# 1.net
KiCad netlist of a schematic drawn in EAGLE
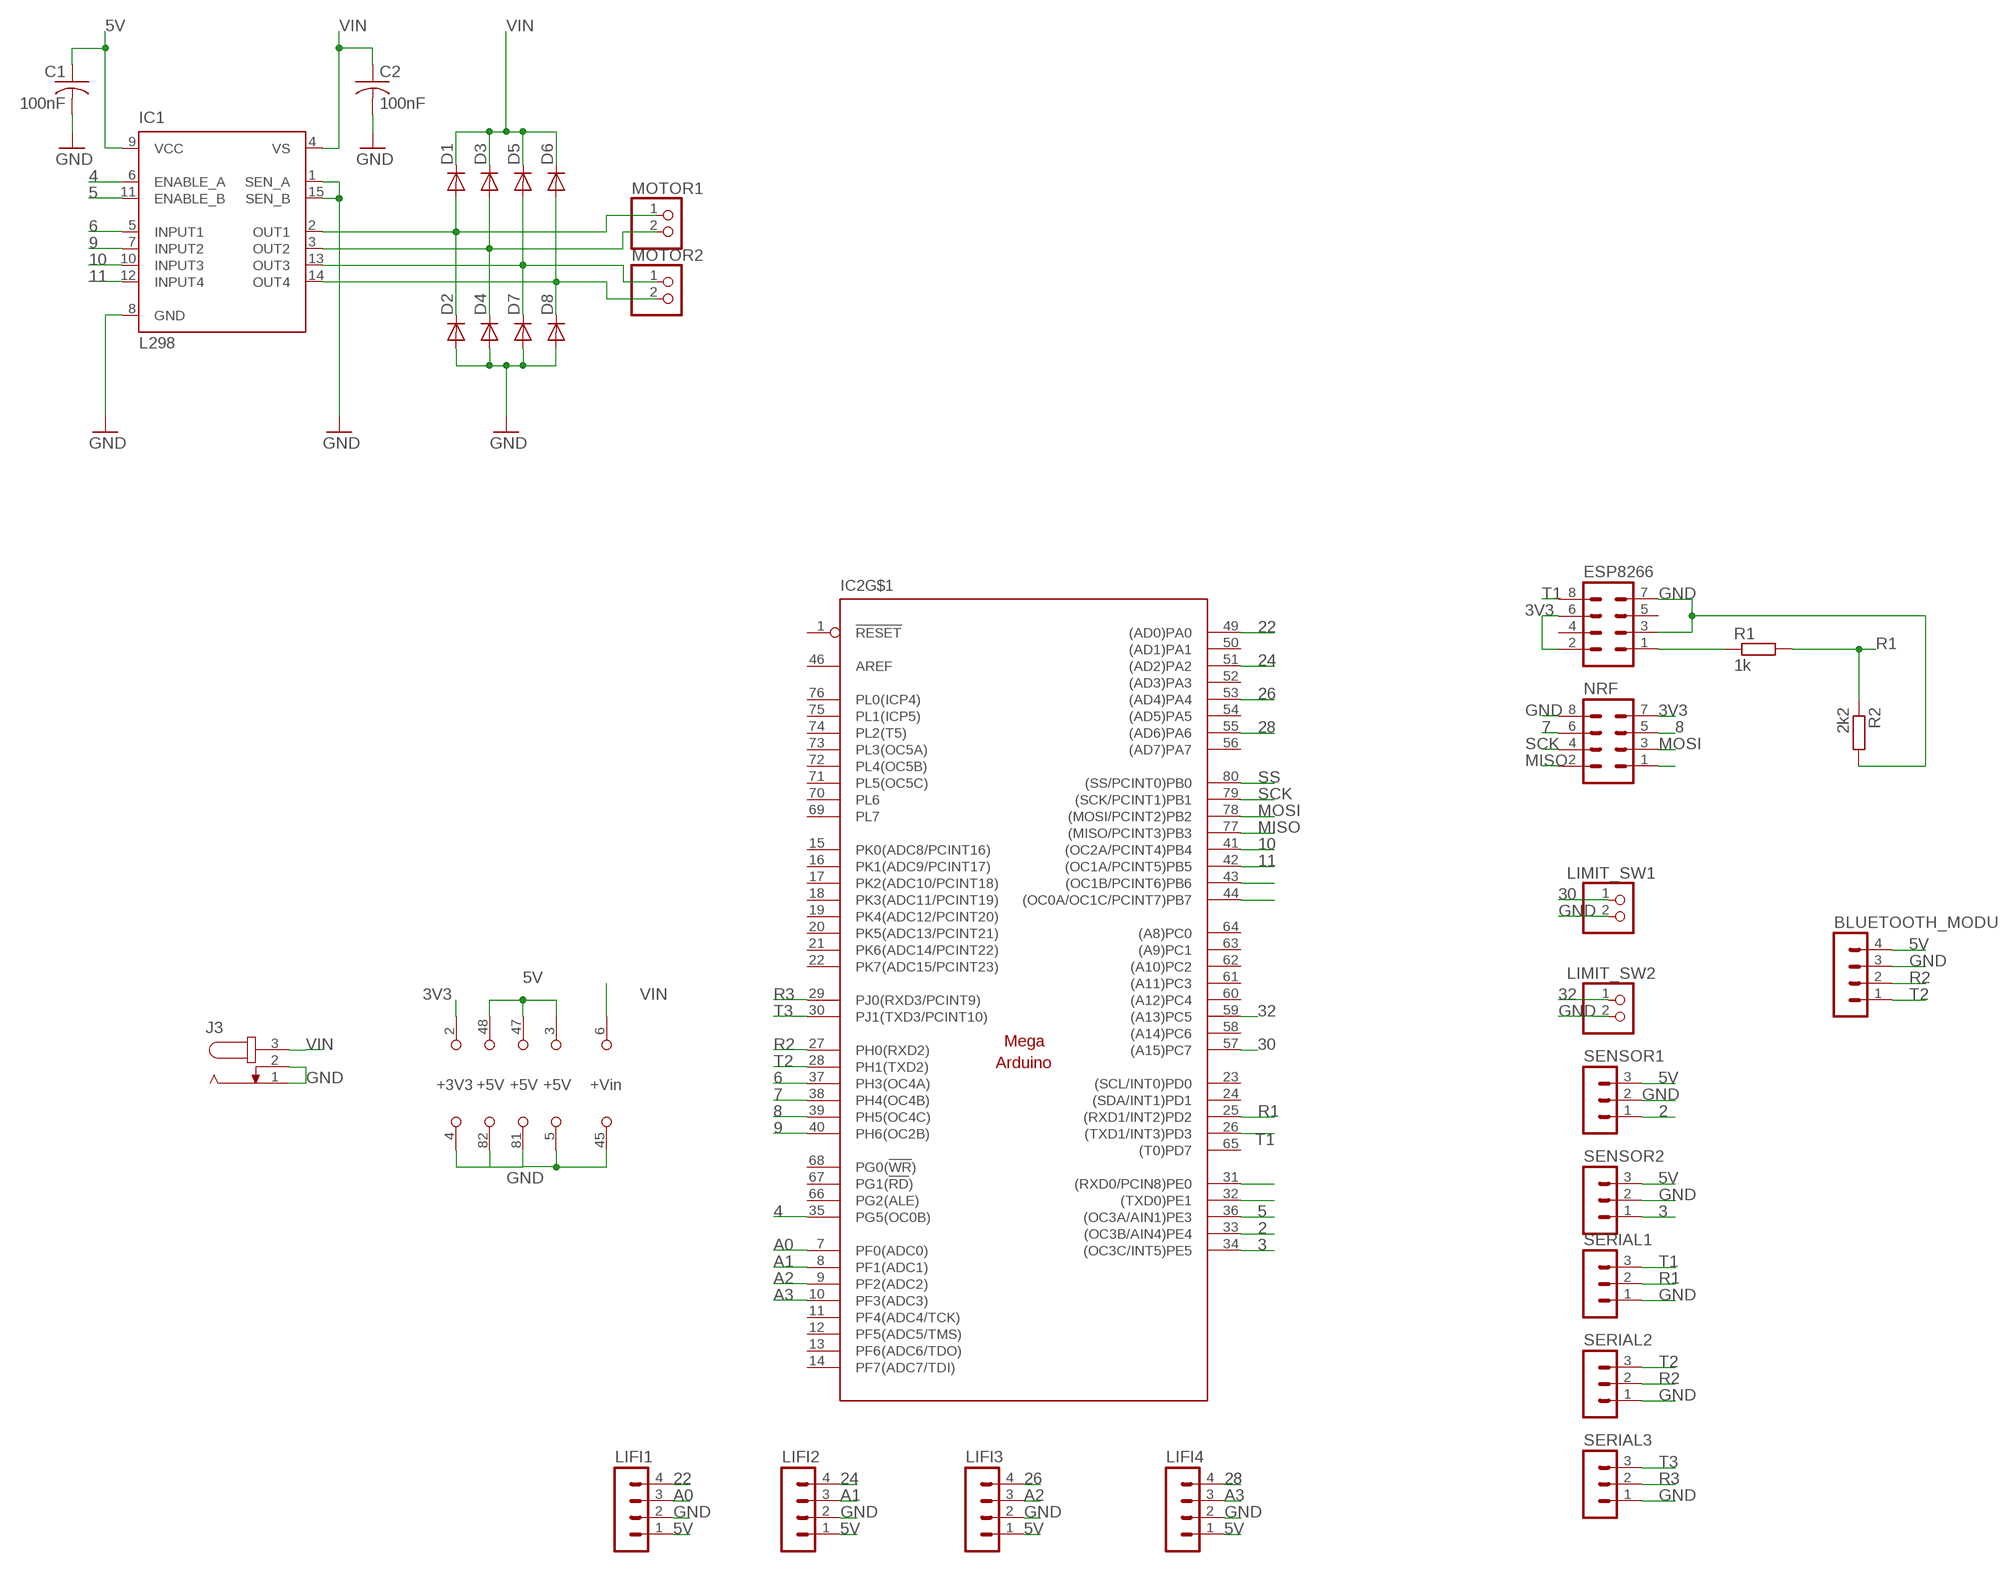
[diagram p0: schematic, sheet 1]

(export (version "E")
  (design (tool "Eeschema 10.0.6"))
  (components
    (comp (ref "BLUETOOTH_MODULE")
      (value "MA04-1")
      (footprint "eagle-import:MA04-1")
      (libsource (lib "eagle-import") (part "MA04-1"))
    )
    (comp (ref "C1")
      (value "100nF")
      (footprint "eagle-import:C050-024X044")
      (libsource (lib "eagle-import") (part "C-US050-024X044"))
    )
    (comp (ref "C2")
      (value "100nF")
      (footprint "eagle-import:C050-024X044")
      (libsource (lib "eagle-import") (part "C-US050-024X044"))
    )
    (comp (ref "D1")
      (value "DIODE-D-5")
      (footprint "eagle-import:D-5")
      (libsource (lib "eagle-import") (part "DIODE-D-5"))
    )
    (comp (ref "D2")
      (value "DIODE-D-5")
      (footprint "eagle-import:D-5")
      (libsource (lib "eagle-import") (part "DIODE-D-5"))
    )
    (comp (ref "D3")
      (value "DIODE-D-5")
      (footprint "eagle-import:D-5")
      (libsource (lib "eagle-import") (part "DIODE-D-5"))
    )
    (comp (ref "D4")
      (value "DIODE-D-5")
      (footprint "eagle-import:D-5")
      (libsource (lib "eagle-import") (part "DIODE-D-5"))
    )
    (comp (ref "D5")
      (value "DIODE-D-5")
      (footprint "eagle-import:D-5")
      (libsource (lib "eagle-import") (part "DIODE-D-5"))
    )
    (comp (ref "D6")
      (value "DIODE-D-5")
      (footprint "eagle-import:D-5")
      (libsource (lib "eagle-import") (part "DIODE-D-5"))
    )
    (comp (ref "D7")
      (value "DIODE-D-5")
      (footprint "eagle-import:D-5")
      (libsource (lib "eagle-import") (part "DIODE-D-5"))
    )
    (comp (ref "D8")
      (value "DIODE-D-5")
      (footprint "eagle-import:D-5")
      (libsource (lib "eagle-import") (part "DIODE-D-5"))
    )
    (comp (ref "ESP8266")
      (value "MA04-2")
      (footprint "eagle-import:MA04-2")
      (libsource (lib "eagle-import") (part "MA04-2"))
    )
    (comp (ref "IC1")
      (value "L298")
      (footprint "eagle-import:MULTIWATT-15")
      (fields (field (name "MPN") "L298N"))
      (libsource (lib "eagle-import") (part "L298"))
    )
    (comp (ref "IC2")
      (value "MEGAARDUINO_21")
      (footprint "eagle-import:MEGA_ARDUINO_1")
      (libsource (lib "eagle-import") (part "MEGAARDUINO_21"))
    )
    (comp (ref "J3")
      (value "JACK-PLUG0")
      (footprint "eagle-import:SPC4077")
      (libsource (lib "eagle-import") (part "JACK-PLUG0"))
    )
    (comp (ref "LIFI1")
      (value "MA04-1")
      (footprint "eagle-import:MA04-1")
      (libsource (lib "eagle-import") (part "MA04-1"))
    )
    (comp (ref "LIFI2")
      (value "MA04-1")
      (footprint "eagle-import:MA04-1")
      (libsource (lib "eagle-import") (part "MA04-1"))
    )
    (comp (ref "LIFI3")
      (value "MA04-1")
      (footprint "eagle-import:MA04-1")
      (libsource (lib "eagle-import") (part "MA04-1"))
    )
    (comp (ref "LIFI4")
      (value "MA04-1")
      (footprint "eagle-import:MA04-1")
      (libsource (lib "eagle-import") (part "MA04-1"))
    )
    (comp (ref "LIMIT_SW1")
      (value "PINHD-1X2")
      (footprint "eagle-import:1X02")
      (libsource (lib "eagle-import") (part "PINHD-1X2"))
    )
    (comp (ref "LIMIT_SW2")
      (value "PINHD-1X2")
      (footprint "eagle-import:1X02")
      (libsource (lib "eagle-import") (part "PINHD-1X2"))
    )
    (comp (ref "MOTOR1")
      (value "PINHD-1X2")
      (footprint "eagle-import:1X02")
      (libsource (lib "eagle-import") (part "PINHD-1X2"))
    )
    (comp (ref "MOTOR2")
      (value "PINHD-1X2")
      (footprint "eagle-import:1X02")
      (libsource (lib "eagle-import") (part "PINHD-1X2"))
    )
    (comp (ref "NRF")
      (value "MA04-2")
      (footprint "eagle-import:MA04-2")
      (libsource (lib "eagle-import") (part "MA04-2"))
    )
    (comp (ref "R1")
      (value "1k")
      (footprint "eagle-import:0204_7")
      (libsource (lib "eagle-import") (part "R-EU_0204/7"))
    )
    (comp (ref "R2")
      (value "2k2")
      (footprint "eagle-import:0204_7")
      (libsource (lib "eagle-import") (part "R-EU_0204/7"))
    )
    (comp (ref "SENSOR1")
      (value "MA03-1")
      (footprint "eagle-import:MA03-1")
      (libsource (lib "eagle-import") (part "MA03-1"))
    )
    (comp (ref "SENSOR2")
      (value "MA03-1")
      (footprint "eagle-import:MA03-1")
      (libsource (lib "eagle-import") (part "MA03-1"))
    )
    (comp (ref "SERIAL1")
      (value "MA03-1")
      (footprint "eagle-import:MA03-1")
      (libsource (lib "eagle-import") (part "MA03-1"))
    )
    (comp (ref "SERIAL2")
      (value "MA03-1")
      (footprint "eagle-import:MA03-1")
      (libsource (lib "eagle-import") (part "MA03-1"))
    )
    (comp (ref "SERIAL3")
      (value "MA03-1")
      (footprint "eagle-import:MA03-1")
      (libsource (lib "eagle-import") (part "MA03-1"))
    )
  )
  (nets
    (net (code "1") (name "/2") (class "Default")
      (node (ref "IC2") (pin "33") (pinfunction "(OC3B/AIN4)PE4_33") (pintype "bidirectional"))
      (node (ref "SENSOR1") (pin "1") (pinfunction "1_1") (pintype "passive"))
    )
    (net (code "2") (name "/3") (class "Default")
      (node (ref "IC2") (pin "34") (pinfunction "(OC3C/INT5)PE5_34") (pintype "bidirectional"))
      (node (ref "SENSOR2") (pin "1") (pinfunction "1_1") (pintype "passive"))
    )
    (net (code "3") (name "/3V3") (class "Default")
      (node (ref "ESP8266") (pin "2") (pinfunction "2_2") (pintype "passive"))
      (node (ref "ESP8266") (pin "6") (pinfunction "6_6") (pintype "passive"))
      (node (ref "IC2") (pin "2") (pinfunction "+3V3_2") (pintype "power_in"))
      (node (ref "NRF") (pin "7") (pinfunction "7_7") (pintype "passive"))
    )
    (net (code "4") (name "/4") (class "Default")
      (node (ref "IC1") (pin "6") (pinfunction "ENABLE_A_6") (pintype "input"))
      (node (ref "IC2") (pin "35") (pinfunction "PG5(OC0B)_35") (pintype "bidirectional"))
    )
    (net (code "5") (name "/5") (class "Default")
      (node (ref "IC1") (pin "11") (pinfunction "ENABLE_B_11") (pintype "input"))
      (node (ref "IC2") (pin "36") (pinfunction "(OC3A/AIN1)PE3_36") (pintype "bidirectional"))
    )
    (net (code "6") (name "/5V") (class "Default")
      (node (ref "BLUETOOTH_MODULE") (pin "4") (pinfunction "4_4") (pintype "passive"))
      (node (ref "C1") (pin "1") (pinfunction "1_1") (pintype "passive"))
      (node (ref "IC1") (pin "9") (pinfunction "VCC_9") (pintype "power_in"))
      (node (ref "IC2") (pin "3") (pinfunction "+5V_3") (pintype "power_in"))
      (node (ref "IC2") (pin "47") (pinfunction "+5V_47") (pintype "power_in"))
      (node (ref "IC2") (pin "48") (pinfunction "+5V_48") (pintype "power_in"))
      (node (ref "LIFI1") (pin "1") (pinfunction "1_1") (pintype "passive"))
      (node (ref "LIFI2") (pin "1") (pinfunction "1_1") (pintype "passive"))
      (node (ref "LIFI3") (pin "1") (pinfunction "1_1") (pintype "passive"))
      (node (ref "LIFI4") (pin "1") (pinfunction "1_1") (pintype "passive"))
      (node (ref "SENSOR1") (pin "3") (pinfunction "3_3") (pintype "passive"))
      (node (ref "SENSOR2") (pin "3") (pinfunction "3_3") (pintype "passive"))
    )
    (net (code "7") (name "/6") (class "Default")
      (node (ref "IC1") (pin "5") (pinfunction "INPUT1_5") (pintype "input"))
      (node (ref "IC2") (pin "37") (pinfunction "PH3(OC4A)_37") (pintype "bidirectional"))
    )
    (net (code "8") (name "/7") (class "Default")
      (node (ref "IC2") (pin "38") (pinfunction "PH4(OC4B)_38") (pintype "bidirectional"))
      (node (ref "NRF") (pin "6") (pinfunction "6_6") (pintype "passive"))
    )
    (net (code "9") (name "/8") (class "Default")
      (node (ref "IC2") (pin "39") (pinfunction "PH5(OC4C)_39") (pintype "bidirectional"))
      (node (ref "NRF") (pin "5") (pinfunction "5_5") (pintype "passive"))
    )
    (net (code "10") (name "/9") (class "Default")
      (node (ref "IC1") (pin "7") (pinfunction "INPUT2_7") (pintype "input"))
      (node (ref "IC2") (pin "40") (pinfunction "PH6(OC2B)_40") (pintype "bidirectional"))
    )
    (net (code "11") (name "/10") (class "Default")
      (node (ref "IC1") (pin "10") (pinfunction "INPUT3_10") (pintype "input"))
      (node (ref "IC2") (pin "41") (pinfunction "(OC2A/PCINT4)PB4_41") (pintype "bidirectional"))
    )
    (net (code "12") (name "/11") (class "Default")
      (node (ref "IC1") (pin "12") (pinfunction "INPUT4_12") (pintype "input"))
      (node (ref "IC2") (pin "42") (pinfunction "(OC1A/PCINT5)PB5_42") (pintype "bidirectional"))
    )
    (net (code "13") (name "/22") (class "Default")
      (node (ref "IC2") (pin "49") (pinfunction "(AD0)PA0_49") (pintype "bidirectional"))
      (node (ref "LIFI1") (pin "4") (pinfunction "4_4") (pintype "passive"))
    )
    (net (code "14") (name "/24") (class "Default")
      (node (ref "IC2") (pin "51") (pinfunction "(AD2)PA2_51") (pintype "bidirectional"))
      (node (ref "LIFI2") (pin "4") (pinfunction "4_4") (pintype "passive"))
    )
    (net (code "15") (name "/26") (class "Default")
      (node (ref "IC2") (pin "53") (pinfunction "(AD4)PA4_53") (pintype "bidirectional"))
      (node (ref "LIFI3") (pin "4") (pinfunction "4_4") (pintype "passive"))
    )
    (net (code "16") (name "/28") (class "Default")
      (node (ref "IC2") (pin "55") (pinfunction "(AD6)PA6_55") (pintype "bidirectional"))
      (node (ref "LIFI4") (pin "4") (pinfunction "4_4") (pintype "passive"))
    )
    (net (code "17") (name "/30") (class "Default")
      (node (ref "IC2") (pin "57") (pinfunction "(A15)PC7_57") (pintype "bidirectional"))
      (node (ref "LIMIT_SW1") (pin "1") (pinfunction "1_1") (pintype "passive"))
    )
    (net (code "18") (name "/32") (class "Default")
      (node (ref "IC2") (pin "59") (pinfunction "(A13)PC5_59") (pintype "bidirectional"))
      (node (ref "LIMIT_SW2") (pin "1") (pinfunction "1_1") (pintype "passive"))
    )
    (net (code "19") (name "/A0") (class "Default")
      (node (ref "IC2") (pin "7") (pinfunction "PF0(ADC0)_7") (pintype "bidirectional"))
      (node (ref "LIFI1") (pin "3") (pinfunction "3_3") (pintype "passive"))
    )
    (net (code "20") (name "/A1") (class "Default")
      (node (ref "IC2") (pin "8") (pinfunction "PF1(ADC1)_8") (pintype "bidirectional"))
      (node (ref "LIFI2") (pin "3") (pinfunction "3_3") (pintype "passive"))
    )
    (net (code "21") (name "/A2") (class "Default")
      (node (ref "IC2") (pin "9") (pinfunction "PF2(ADC2)_9") (pintype "bidirectional"))
      (node (ref "LIFI3") (pin "3") (pinfunction "3_3") (pintype "passive"))
    )
    (net (code "22") (name "/A3") (class "Default")
      (node (ref "IC2") (pin "10") (pinfunction "PF3(ADC3)_10") (pintype "bidirectional"))
      (node (ref "LIFI4") (pin "3") (pinfunction "3_3") (pintype "passive"))
    )
    (net (code "23") (name "/MISO") (class "Default")
      (node (ref "IC2") (pin "77") (pinfunction "(MISO/PCINT3)PB3_77") (pintype "bidirectional"))
      (node (ref "NRF") (pin "2") (pinfunction "2_2") (pintype "passive"))
    )
    (net (code "24") (name "/MOSI") (class "Default")
      (node (ref "IC2") (pin "78") (pinfunction "(MOSI/PCINT2)PB2_78") (pintype "bidirectional"))
      (node (ref "NRF") (pin "3") (pinfunction "3_3") (pintype "passive"))
    )
    (net (code "25") (name "/R1") (class "Default")
      (node (ref "IC2") (pin "25") (pinfunction "(RXD1/INT2)PD2_25") (pintype "bidirectional"))
      (node (ref "R1") (pin "2") (pinfunction "2_2") (pintype "passive"))
      (node (ref "R2") (pin "1") (pinfunction "1_1") (pintype "passive"))
      (node (ref "SERIAL1") (pin "2") (pinfunction "2_2") (pintype "passive"))
    )
    (net (code "26") (name "/R2") (class "Default")
      (node (ref "BLUETOOTH_MODULE") (pin "2") (pinfunction "2_2") (pintype "passive"))
      (node (ref "IC2") (pin "27") (pinfunction "PH0(RXD2)_27") (pintype "bidirectional"))
      (node (ref "SERIAL2") (pin "2") (pinfunction "2_2") (pintype "passive"))
    )
    (net (code "27") (name "/R3") (class "Default")
      (node (ref "IC2") (pin "29") (pinfunction "PJ0(RXD3/PCINT9)_29") (pintype "bidirectional"))
      (node (ref "SERIAL3") (pin "2") (pinfunction "2_2") (pintype "passive"))
    )
    (net (code "28") (name "/SCK") (class "Default")
      (node (ref "IC2") (pin "79") (pinfunction "(SCK/PCINT1)PB1_79") (pintype "bidirectional"))
      (node (ref "NRF") (pin "4") (pinfunction "4_4") (pintype "passive"))
    )
    (net (code "29") (name "/SS") (class "Default")
      (node (ref "IC2") (pin "80") (pinfunction "(SS/PCINT0)PB0_80") (pintype "bidirectional"))
    )
    (net (code "30") (name "/T1") (class "Default")
      (node (ref "ESP8266") (pin "8") (pinfunction "8_8") (pintype "passive"))
      (node (ref "IC2") (pin "26") (pinfunction "(TXD1/INT3)PD3_26") (pintype "bidirectional"))
      (node (ref "SERIAL1") (pin "3") (pinfunction "3_3") (pintype "passive"))
    )
    (net (code "31") (name "/T2") (class "Default")
      (node (ref "BLUETOOTH_MODULE") (pin "1") (pinfunction "1_1") (pintype "passive"))
      (node (ref "IC2") (pin "28") (pinfunction "PH1(TXD2)_28") (pintype "bidirectional"))
      (node (ref "SERIAL2") (pin "3") (pinfunction "3_3") (pintype "passive"))
    )
    (net (code "32") (name "/T3") (class "Default")
      (node (ref "IC2") (pin "30") (pinfunction "PJ1(TXD3/PCINT10)_30") (pintype "bidirectional"))
      (node (ref "SERIAL3") (pin "3") (pinfunction "3_3") (pintype "passive"))
    )
    (net (code "33") (name "/VIN") (class "Default")
      (node (ref "C2") (pin "1") (pinfunction "1_1") (pintype "passive"))
      (node (ref "D1") (pin "C") (pinfunction "C_C") (pintype "passive"))
      (node (ref "D3") (pin "C") (pinfunction "C_C") (pintype "passive"))
      (node (ref "D5") (pin "C") (pinfunction "C_C") (pintype "passive"))
      (node (ref "D6") (pin "C") (pinfunction "C_C") (pintype "passive"))
      (node (ref "IC1") (pin "4") (pinfunction "VS_4") (pintype "power_in"))
      (node (ref "IC2") (pin "6") (pinfunction "+VIN_6") (pintype "power_in"))
      (node (ref "J3") (pin "3") (pinfunction "3_3") (pintype "passive"))
    )
    (net (code "34") (name "GND") (class "Default")
      (node (ref "BLUETOOTH_MODULE") (pin "3") (pinfunction "3_3") (pintype "passive"))
      (node (ref "C1") (pin "2") (pinfunction "2_2") (pintype "passive"))
      (node (ref "C2") (pin "2") (pinfunction "2_2") (pintype "passive"))
      (node (ref "D2") (pin "A") (pinfunction "A_A") (pintype "passive"))
      (node (ref "D4") (pin "A") (pinfunction "A_A") (pintype "passive"))
      (node (ref "D7") (pin "A") (pinfunction "A_A") (pintype "passive"))
      (node (ref "D8") (pin "A") (pinfunction "A_A") (pintype "passive"))
      (node (ref "ESP8266") (pin "3") (pinfunction "3_3") (pintype "passive"))
      (node (ref "ESP8266") (pin "7") (pinfunction "7_7") (pintype "passive"))
      (node (ref "IC1") (pin "1") (pinfunction "SEN_A_1") (pintype "input"))
      (node (ref "IC1") (pin "15") (pinfunction "SEN_B_15") (pintype "input"))
      (node (ref "IC1") (pin "8") (pinfunction "GND_8") (pintype "power_in"))
      (node (ref "IC2") (pin "4") (pinfunction "GND_4") (pintype "power_in"))
      (node (ref "IC2") (pin "45") (pinfunction "GND_45") (pintype "power_in"))
      (node (ref "IC2") (pin "5") (pinfunction "GND_5") (pintype "power_in"))
      (node (ref "IC2") (pin "81") (pinfunction "GND_81") (pintype "power_in"))
      (node (ref "IC2") (pin "82") (pinfunction "GND_82") (pintype "power_in"))
      (node (ref "J3") (pin "1") (pinfunction "1_1") (pintype "passive"))
      (node (ref "J3") (pin "2") (pinfunction "2_2") (pintype "passive"))
      (node (ref "LIFI1") (pin "2") (pinfunction "2_2") (pintype "passive"))
      (node (ref "LIFI2") (pin "2") (pinfunction "2_2") (pintype "passive"))
      (node (ref "LIFI3") (pin "2") (pinfunction "2_2") (pintype "passive"))
      (node (ref "LIFI4") (pin "2") (pinfunction "2_2") (pintype "passive"))
      (node (ref "LIMIT_SW1") (pin "2") (pinfunction "2_2") (pintype "passive"))
      (node (ref "LIMIT_SW2") (pin "2") (pinfunction "2_2") (pintype "passive"))
      (node (ref "NRF") (pin "8") (pinfunction "8_8") (pintype "passive"))
      (node (ref "R2") (pin "2") (pinfunction "2_2") (pintype "passive"))
      (node (ref "SENSOR1") (pin "2") (pinfunction "2_2") (pintype "passive"))
      (node (ref "SENSOR2") (pin "2") (pinfunction "2_2") (pintype "passive"))
      (node (ref "SERIAL1") (pin "1") (pinfunction "1_1") (pintype "passive"))
      (node (ref "SERIAL2") (pin "1") (pinfunction "1_1") (pintype "passive"))
      (node (ref "SERIAL3") (pin "1") (pinfunction "1_1") (pintype "passive"))
    )
    (net (code "35") (name "Net-(ESP8266-Pad1)") (class "Default")
      (node (ref "ESP8266") (pin "1") (pinfunction "1_1") (pintype "passive"))
      (node (ref "R1") (pin "1") (pinfunction "1_1") (pintype "passive"))
    )
    (net (code "36") (name "Net-(IC1-OUT1)") (class "Default")
      (node (ref "D1") (pin "A") (pinfunction "A_A") (pintype "passive"))
      (node (ref "D2") (pin "C") (pinfunction "C_C") (pintype "passive"))
      (node (ref "IC1") (pin "2") (pinfunction "OUT1_2") (pintype "output"))
      (node (ref "MOTOR1") (pin "1") (pinfunction "1_1") (pintype "passive"))
    )
    (net (code "37") (name "Net-(IC1-OUT2)") (class "Default")
      (node (ref "D3") (pin "A") (pinfunction "A_A") (pintype "passive"))
      (node (ref "D4") (pin "C") (pinfunction "C_C") (pintype "passive"))
      (node (ref "IC1") (pin "3") (pinfunction "OUT2_3") (pintype "output"))
      (node (ref "MOTOR1") (pin "2") (pinfunction "2_2") (pintype "passive"))
    )
    (net (code "38") (name "Net-(IC1-OUT3)") (class "Default")
      (node (ref "D5") (pin "A") (pinfunction "A_A") (pintype "passive"))
      (node (ref "D7") (pin "C") (pinfunction "C_C") (pintype "passive"))
      (node (ref "IC1") (pin "13") (pinfunction "OUT3_13") (pintype "output"))
      (node (ref "MOTOR2") (pin "1") (pinfunction "1_1") (pintype "passive"))
    )
    (net (code "39") (name "Net-(IC1-OUT4)") (class "Default")
      (node (ref "D6") (pin "A") (pinfunction "A_A") (pintype "passive"))
      (node (ref "D8") (pin "C") (pinfunction "C_C") (pintype "passive"))
      (node (ref "IC1") (pin "14") (pinfunction "OUT4_14") (pintype "output"))
      (node (ref "MOTOR2") (pin "2") (pinfunction "2_2") (pintype "passive"))
    )
    (net (code "40") (name "unconnected-(ESP8266-Pad4)") (class "Default")
      (node (ref "ESP8266") (pin "4") (pinfunction "4_4") (pintype "passive"))
    )
    (net (code "41") (name "unconnected-(ESP8266-Pad5)") (class "Default")
      (node (ref "ESP8266") (pin "5") (pinfunction "5_5") (pintype "passive"))
    )
    (net (code "42") (name "unconnected-(IC2A-(A8)PC0-Pad64)") (class "Default")
      (node (ref "IC2") (pin "64") (pinfunction "(A8)PC0_64") (pintype "bidirectional"))
    )
    (net (code "43") (name "unconnected-(IC2A-(A9)PC1-Pad63)") (class "Default")
      (node (ref "IC2") (pin "63") (pinfunction "(A9)PC1_63") (pintype "bidirectional"))
    )
    (net (code "44") (name "unconnected-(IC2A-(A10)PC2-Pad62)") (class "Default")
      (node (ref "IC2") (pin "62") (pinfunction "(A10)PC2_62") (pintype "bidirectional"))
    )
    (net (code "45") (name "unconnected-(IC2A-(A11)PC3-Pad61)") (class "Default")
      (node (ref "IC2") (pin "61") (pinfunction "(A11)PC3_61") (pintype "bidirectional"))
    )
    (net (code "46") (name "unconnected-(IC2A-(A12)PC4-Pad60)") (class "Default")
      (node (ref "IC2") (pin "60") (pinfunction "(A12)PC4_60") (pintype "bidirectional"))
    )
    (net (code "47") (name "unconnected-(IC2A-(A14)PC6-Pad58)") (class "Default")
      (node (ref "IC2") (pin "58") (pinfunction "(A14)PC6_58") (pintype "bidirectional"))
    )
    (net (code "48") (name "unconnected-(IC2A-(AD1)PA1-Pad50)") (class "Default")
      (node (ref "IC2") (pin "50") (pinfunction "(AD1)PA1_50") (pintype "bidirectional"))
    )
    (net (code "49") (name "unconnected-(IC2A-(AD3)PA3-Pad52)") (class "Default")
      (node (ref "IC2") (pin "52") (pinfunction "(AD3)PA3_52") (pintype "bidirectional"))
    )
    (net (code "50") (name "unconnected-(IC2A-(AD5)PA5-Pad54)") (class "Default")
      (node (ref "IC2") (pin "54") (pinfunction "(AD5)PA5_54") (pintype "bidirectional"))
    )
    (net (code "51") (name "unconnected-(IC2A-(AD7)PA7-Pad56)") (class "Default")
      (node (ref "IC2") (pin "56") (pinfunction "(AD7)PA7_56") (pintype "bidirectional"))
    )
    (net (code "52") (name "unconnected-(IC2A-(OC0A{slash}OC1C{slash}PCINT7)PB7-Pad44)") (class "Default")
      (node (ref "IC2") (pin "44") (pinfunction "(OC0A/OC1C/PCINT7)PB7_44") (pintype "bidirectional"))
    )
    (net (code "53") (name "unconnected-(IC2A-(OC1B{slash}PCINT6)PB6-Pad43)") (class "Default")
      (node (ref "IC2") (pin "43") (pinfunction "(OC1B/PCINT6)PB6_43") (pintype "bidirectional"))
    )
    (net (code "54") (name "unconnected-(IC2A-(RXD0{slash}PCIN8)PE0-Pad31)") (class "Default")
      (node (ref "IC2") (pin "31") (pinfunction "(RXD0/PCIN8)PE0_31") (pintype "bidirectional"))
    )
    (net (code "55") (name "unconnected-(IC2A-(SCL{slash}INT0)PD0-Pad23)") (class "Default")
      (node (ref "IC2") (pin "23") (pinfunction "(SCL/INT0)PD0_23") (pintype "bidirectional"))
    )
    (net (code "56") (name "unconnected-(IC2A-(SDA{slash}INT1)PD1-Pad24)") (class "Default")
      (node (ref "IC2") (pin "24") (pinfunction "(SDA/INT1)PD1_24") (pintype "bidirectional"))
    )
    (net (code "57") (name "unconnected-(IC2A-(T0)PD7-Pad65)") (class "Default")
      (node (ref "IC2") (pin "65") (pinfunction "(T0)PD7_65") (pintype "bidirectional"))
    )
    (net (code "58") (name "unconnected-(IC2A-(TXD0)PE1-Pad32)") (class "Default")
      (node (ref "IC2") (pin "32") (pinfunction "(TXD0)PE1_32") (pintype "bidirectional"))
    )
    (net (code "59") (name "unconnected-(IC2A-AREF-Pad46)") (class "Default")
      (node (ref "IC2") (pin "46") (pinfunction "AREF_46") (pintype "bidirectional"))
    )
    (net (code "60") (name "unconnected-(IC2A-PF4(ADC4{slash}TCK)-Pad11)") (class "Default")
      (node (ref "IC2") (pin "11") (pinfunction "PF4(ADC4/TCK)_11") (pintype "bidirectional"))
    )
    (net (code "61") (name "unconnected-(IC2A-PF5(ADC5{slash}TMS)-Pad12)") (class "Default")
      (node (ref "IC2") (pin "12") (pinfunction "PF5(ADC5/TMS)_12") (pintype "bidirectional"))
    )
    (net (code "62") (name "unconnected-(IC2A-PF6(ADC6{slash}TDO)-Pad13)") (class "Default")
      (node (ref "IC2") (pin "13") (pinfunction "PF6(ADC6/TDO)_13") (pintype "bidirectional"))
    )
    (net (code "63") (name "unconnected-(IC2A-PF7(ADC7{slash}TDI)-Pad14)") (class "Default")
      (node (ref "IC2") (pin "14") (pinfunction "PF7(ADC7/TDI)_14") (pintype "bidirectional"))
    )
    (net (code "64") (name "unconnected-(IC2A-PG0(~{WR})-Pad68)") (class "Default")
      (node (ref "IC2") (pin "68") (pinfunction "PG0(~{WR})_68") (pintype "bidirectional"))
    )
    (net (code "65") (name "unconnected-(IC2A-PG1(~{RD})-Pad67)") (class "Default")
      (node (ref "IC2") (pin "67") (pinfunction "PG1(~{RD})_67") (pintype "bidirectional"))
    )
    (net (code "66") (name "unconnected-(IC2A-PG2(ALE)-Pad66)") (class "Default")
      (node (ref "IC2") (pin "66") (pinfunction "PG2(ALE)_66") (pintype "bidirectional"))
    )
    (net (code "67") (name "unconnected-(IC2A-PK0(ADC8{slash}PCINT16)-Pad15)") (class "Default")
      (node (ref "IC2") (pin "15") (pinfunction "PK0(ADC8/PCINT16)_15") (pintype "bidirectional"))
    )
    (net (code "68") (name "unconnected-(IC2A-PK1(ADC9{slash}PCINT17)-Pad16)") (class "Default")
      (node (ref "IC2") (pin "16") (pinfunction "PK1(ADC9/PCINT17)_16") (pintype "bidirectional"))
    )
    (net (code "69") (name "unconnected-(IC2A-PK2(ADC10{slash}PCINT18)-Pad17)") (class "Default")
      (node (ref "IC2") (pin "17") (pinfunction "PK2(ADC10/PCINT18)_17") (pintype "bidirectional"))
    )
    (net (code "70") (name "unconnected-(IC2A-PK3(ADC11{slash}PCINT19)-Pad18)") (class "Default")
      (node (ref "IC2") (pin "18") (pinfunction "PK3(ADC11/PCINT19)_18") (pintype "bidirectional"))
    )
    (net (code "71") (name "unconnected-(IC2A-PK4(ADC12{slash}PCINT20)-Pad19)") (class "Default")
      (node (ref "IC2") (pin "19") (pinfunction "PK4(ADC12/PCINT20)_19") (pintype "bidirectional"))
    )
    (net (code "72") (name "unconnected-(IC2A-PK5(ADC13{slash}PCINT21)-Pad20)") (class "Default")
      (node (ref "IC2") (pin "20") (pinfunction "PK5(ADC13/PCINT21)_20") (pintype "bidirectional"))
    )
    (net (code "73") (name "unconnected-(IC2A-PK6(ADC14{slash}PCINT22)-Pad21)") (class "Default")
      (node (ref "IC2") (pin "21") (pinfunction "PK6(ADC14/PCINT22)_21") (pintype "bidirectional"))
    )
    (net (code "74") (name "unconnected-(IC2A-PK7(ADC15{slash}PCINT23)-Pad22)") (class "Default")
      (node (ref "IC2") (pin "22") (pinfunction "PK7(ADC15/PCINT23)_22") (pintype "bidirectional"))
    )
    (net (code "75") (name "unconnected-(IC2A-PL0(ICP4)-Pad76)") (class "Default")
      (node (ref "IC2") (pin "76") (pinfunction "PL0(ICP4)_76") (pintype "bidirectional"))
    )
    (net (code "76") (name "unconnected-(IC2A-PL1(ICP5)-Pad75)") (class "Default")
      (node (ref "IC2") (pin "75") (pinfunction "PL1(ICP5)_75") (pintype "bidirectional"))
    )
    (net (code "77") (name "unconnected-(IC2A-PL2(T5)-Pad74)") (class "Default")
      (node (ref "IC2") (pin "74") (pinfunction "PL2(T5)_74") (pintype "bidirectional"))
    )
    (net (code "78") (name "unconnected-(IC2A-PL3(OC5A)-Pad73)") (class "Default")
      (node (ref "IC2") (pin "73") (pinfunction "PL3(OC5A)_73") (pintype "bidirectional"))
    )
    (net (code "79") (name "unconnected-(IC2A-PL4(OC5B)-Pad72)") (class "Default")
      (node (ref "IC2") (pin "72") (pinfunction "PL4(OC5B)_72") (pintype "bidirectional"))
    )
    (net (code "80") (name "unconnected-(IC2A-PL5(OC5C)-Pad71)") (class "Default")
      (node (ref "IC2") (pin "71") (pinfunction "PL5(OC5C)_71") (pintype "bidirectional"))
    )
    (net (code "81") (name "unconnected-(IC2A-PL6-Pad70)") (class "Default")
      (node (ref "IC2") (pin "70") (pinfunction "PL6_70") (pintype "bidirectional"))
    )
    (net (code "82") (name "unconnected-(IC2A-PL7-Pad69)") (class "Default")
      (node (ref "IC2") (pin "69") (pinfunction "PL7_69") (pintype "bidirectional"))
    )
    (net (code "83") (name "unconnected-(IC2A-~{RESET}-Pad1)") (class "Default")
      (node (ref "IC2") (pin "1") (pinfunction "~{RESET}_1") (pintype "bidirectional"))
    )
    (net (code "84") (name "unconnected-(NRF-Pad1)") (class "Default")
      (node (ref "NRF") (pin "1") (pinfunction "1_1") (pintype "passive"))
    )
  )
)
